# 1A20J5_1A21J6_A.net
KiCad netlist of a schematic drawn in Altium Designer
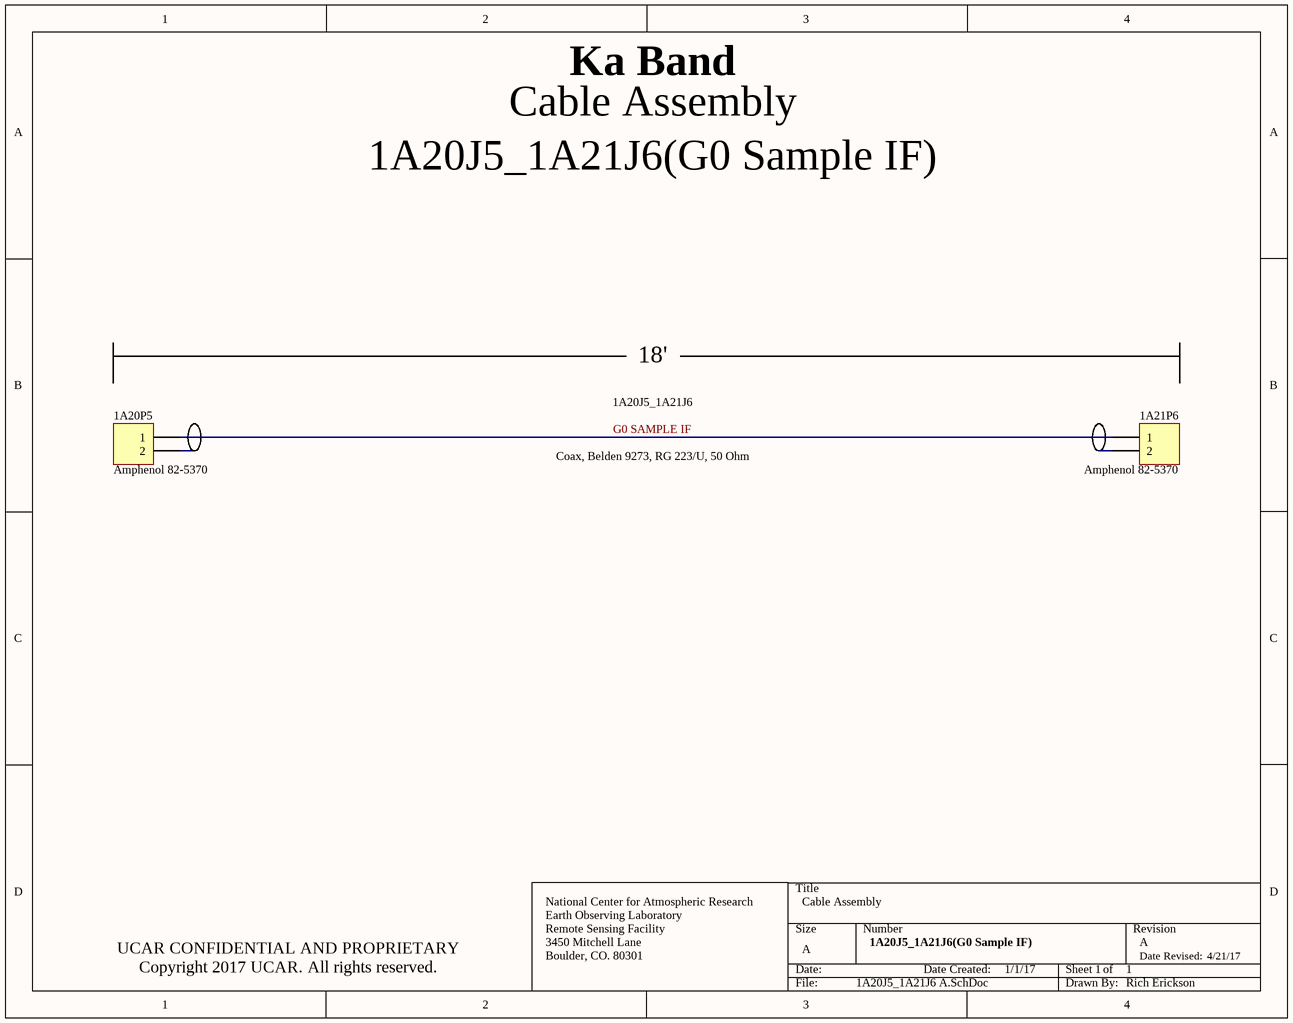
[diagram p0: 1A20J5_1A21J6 A.SchDoc]

(export (version "E")
  (design (tool "Eeschema 10.0.6"))
  (components
    (comp (ref "1A20P5")
      (value "Amphenol 82-5370")
      (footprint "HDR1X2")
      (description "Header, 2-Pin")
      (fields (field (name "PUBLISHER") "Altium Limited"))
      (libsource (lib "Miscellaneous Connectors") (part "Header 2"))
    )
    (comp (ref "1A21P6")
      (value "Amphenol 82-5370")
      (footprint "HDR1X2")
      (description "Header, 2-Pin")
      (fields (field (name "PUBLISHER") "Altium Limited"))
      (libsource (lib "") (part "Header 2_1"))
    )
  )
  (nets
    (net (code "1") (name "/G0 SAMPLE IF") (class "Default")
      (node (ref "1A20P5") (pin "1") (pinfunction "1_1") (pintype "passive"))
      (node (ref "1A21P6") (pin "1") (pinfunction "1_1") (pintype "passive"))
    )
    (net (code "2") (name "unconnected-(1A20P5-Pad2)") (class "Default")
      (node (ref "1A20P5") (pin "2") (pinfunction "2_2") (pintype "passive"))
    )
    (net (code "3") (name "unconnected-(1A21P6-Pad2)") (class "Default")
      (node (ref "1A21P6") (pin "2") (pinfunction "2_2") (pintype "passive"))
    )
  )
)
